# tin_of_fets.net
KiCad netlist of a schematic drawn in EAGLE
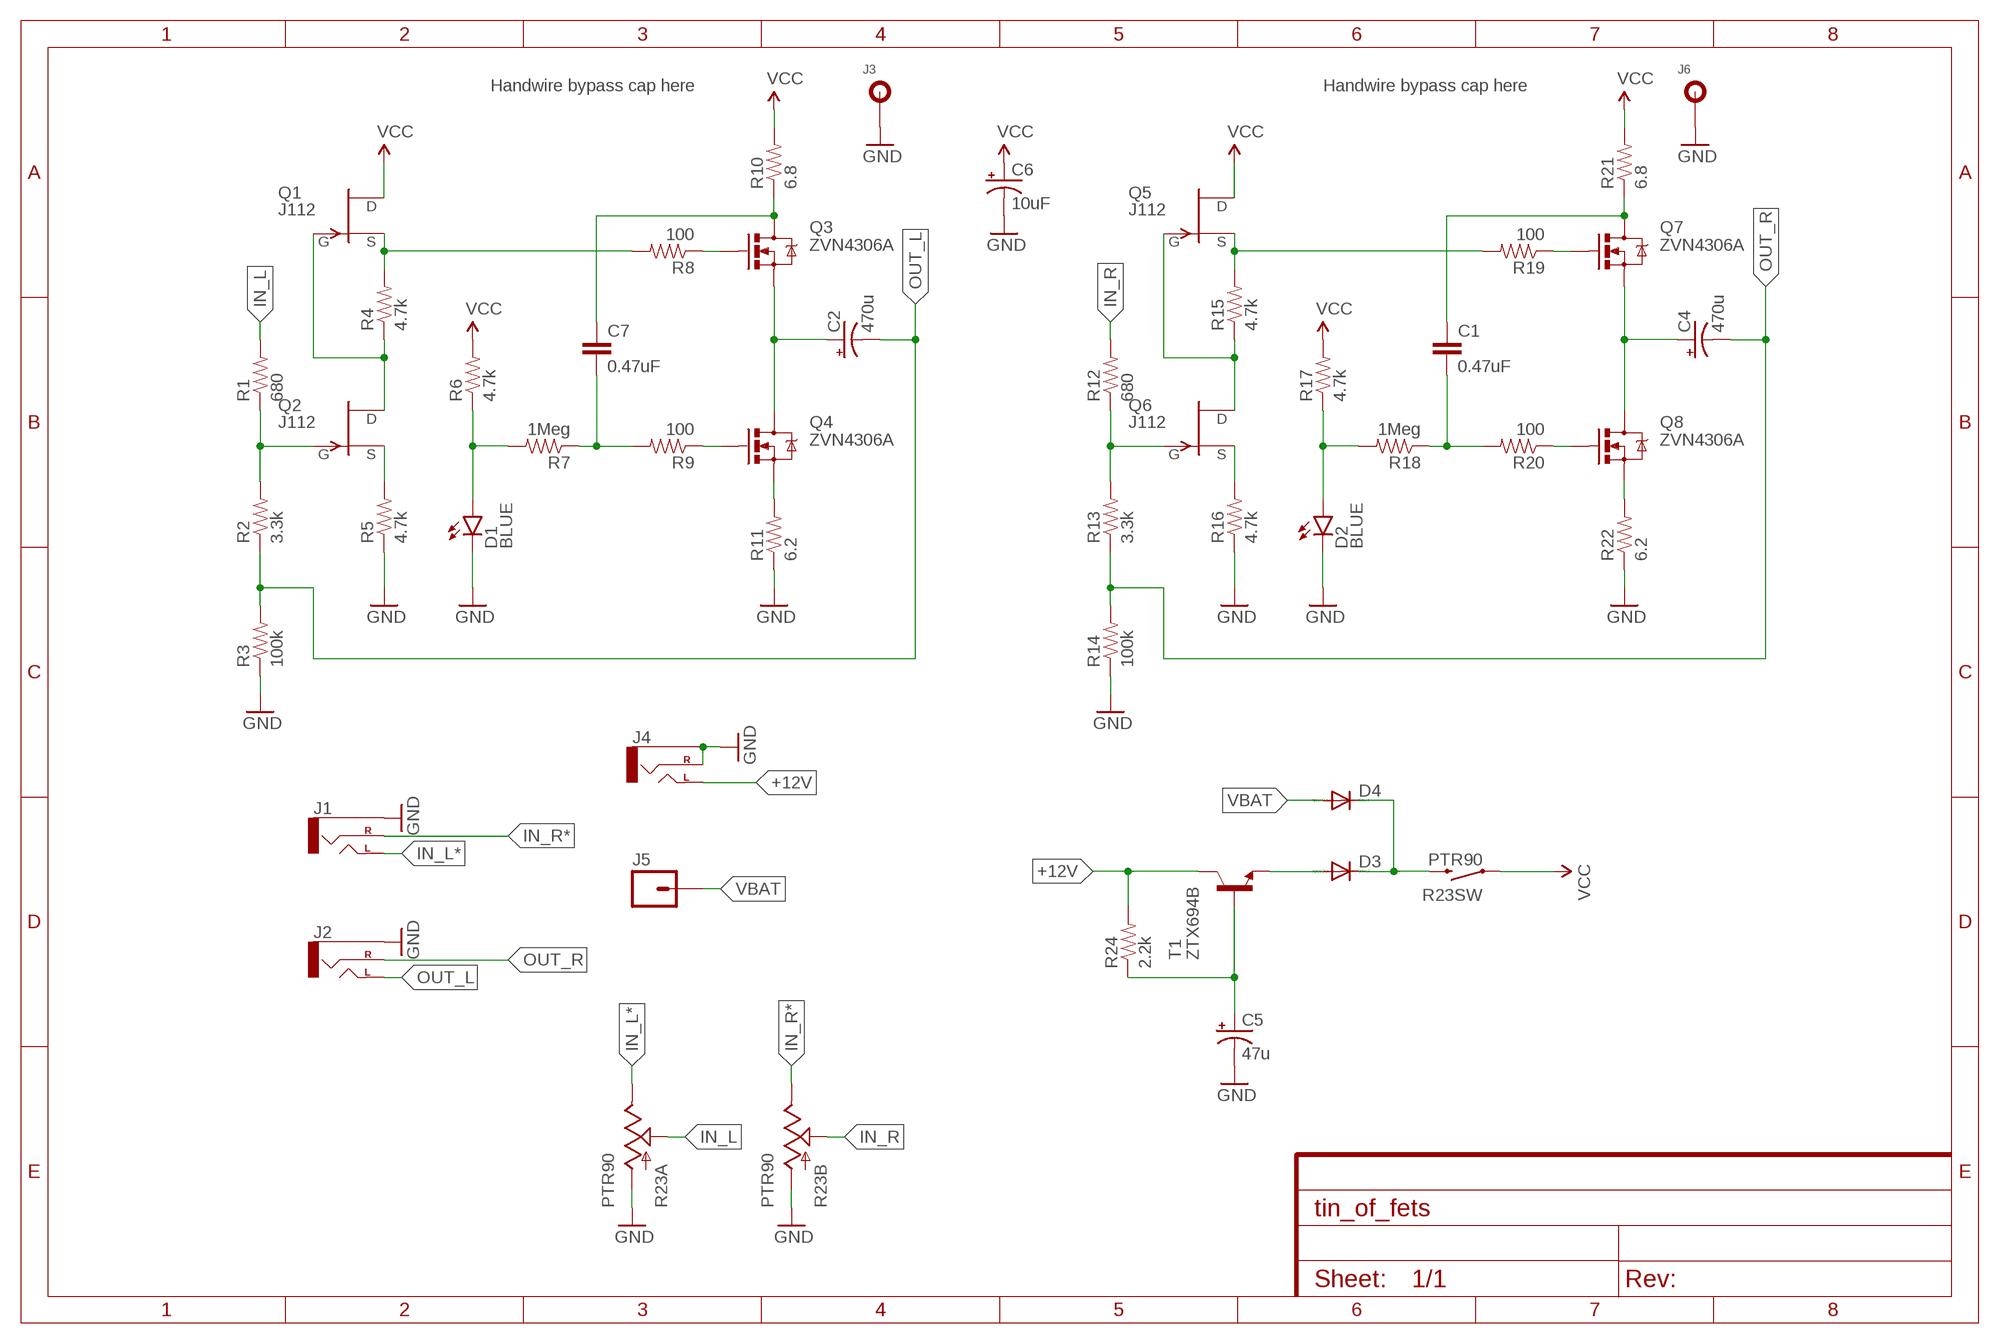
[diagram p0: schematic, sheet 1]

(export (version "E")
  (design (tool "Eeschema 10.0.6"))
  (components
    (comp (ref "A1")
      (value "9V-BATTERY-DOCU")
      (footprint "eagle-import:9V-BATTERY-DIM")
      (libsource (lib "eagle-import") (part "9V-BATTERY-DOCU"))
    )
    (comp (ref "A2")
      (value "9V-BATTERY-DOCU")
      (footprint "eagle-import:9V-BATTERY-DIM")
      (libsource (lib "eagle-import") (part "9V-BATTERY-DOCU"))
    )
    (comp (ref "A3")
      (value "ALTOIDS-DOCU")
      (footprint "eagle-import:ALTOIDS-INNER-DIM")
      (libsource (lib "eagle-import") (part "ALTOIDS-DOCU"))
    )
    (comp (ref "C1")
      (value "0.47uF")
      (footprint "eagle-import:C5B3.5")
      (libsource (lib "eagle-import") (part "C5/3.5"))
    )
    (comp (ref "C2")
      (value "470u")
      (footprint "eagle-import:CPOL-RADIAL-1000UF-25V")
      (libsource (lib "eagle-import") (part "CAP_POLPTH4"))
    )
    (comp (ref "C4")
      (value "470u")
      (footprint "eagle-import:CPOL-RADIAL-1000UF-25V")
      (libsource (lib "eagle-import") (part "CAP_POLPTH4"))
    )
    (comp (ref "C5")
      (value "47u")
      (footprint "eagle-import:CPOL-RADIAL-10UF-25V")
      (libsource (lib "eagle-import") (part "CAP_POLPTH2"))
    )
    (comp (ref "C6")
      (value "10uF")
      (footprint "eagle-import:CPOL-RADIAL-10UF-25V")
      (libsource (lib "eagle-import") (part "CAP_POLPTH2"))
    )
    (comp (ref "C7")
      (value "0.47uF")
      (footprint "eagle-import:C5B3.5")
      (libsource (lib "eagle-import") (part "C5/3.5"))
    )
    (comp (ref "D1")
      (value "BLUE")
      (footprint "eagle-import:LED3MM")
      (libsource (lib "eagle-import") (part "LED3MM"))
    )
    (comp (ref "D2")
      (value "BLUE")
      (footprint "eagle-import:LED3MM")
      (libsource (lib "eagle-import") (part "LED3MM"))
    )
    (comp (ref "D3")
      (value "DIODE-C1702-05")
      (footprint "eagle-import:C1702-05")
      (libsource (lib "eagle-import") (part "DIODE-C1702-05"))
    )
    (comp (ref "D4")
      (value "DIODE-C1702-05")
      (footprint "eagle-import:C1702-05")
      (libsource (lib "eagle-import") (part "DIODE-C1702-05"))
    )
    (comp (ref "J1")
      (value "AUDIO-JACK2.5MM")
      (footprint "eagle-import:STEREOJACK2.5MM_STEREOJACK2.5MM")
      (libsource (lib "eagle-import") (part "AUDIO-JACK2.5MM"))
    )
    (comp (ref "J2")
      (value "AUDIO-JACK2.5MM")
      (footprint "eagle-import:STEREOJACK2.5MM_STEREOJACK2.5MM")
      (libsource (lib "eagle-import") (part "AUDIO-JACK2.5MM"))
    )
    (comp (ref "J3")
      (value "PAD-NO-THERMAL")
      (footprint "eagle-import:PAD-NO-THERMAL")
      (libsource (lib "eagle-import") (part "PAD-NO-THERMAL"))
    )
    (comp (ref "J4")
      (value "AUDIO-JACK2.5MM")
      (footprint "eagle-import:STEREOJACK2.5MM_STEREOJACK2.5MM")
      (libsource (lib "eagle-import") (part "AUDIO-JACK2.5MM"))
    )
    (comp (ref "J5")
      (value "M01PTH")
      (footprint "eagle-import:1X01")
      (libsource (lib "eagle-import") (part "M01PTH"))
    )
    (comp (ref "J6")
      (value "PAD-NO-THERMAL")
      (footprint "eagle-import:PAD-NO-THERMAL")
      (libsource (lib "eagle-import") (part "PAD-NO-THERMAL"))
    )
    (comp (ref "Q1")
      (value "J112")
      (footprint "eagle-import:TO92")
      (libsource (lib "eagle-import") (part "?20J1"))
    )
    (comp (ref "Q2")
      (value "J112")
      (footprint "eagle-import:TO92")
      (libsource (lib "eagle-import") (part "?20J1"))
    )
    (comp (ref "Q3")
      (value "ZVN4306A")
      (footprint "eagle-import:TO-92")
      (libsource (lib "eagle-import") (part "MOSFET-NCHANNEL2N7000"))
    )
    (comp (ref "Q4")
      (value "ZVN4306A")
      (footprint "eagle-import:TO-92")
      (libsource (lib "eagle-import") (part "MOSFET-NCHANNEL2N7000"))
    )
    (comp (ref "Q5")
      (value "J112")
      (footprint "eagle-import:TO92")
      (libsource (lib "eagle-import") (part "?20J1"))
    )
    (comp (ref "Q6")
      (value "J112")
      (footprint "eagle-import:TO92")
      (libsource (lib "eagle-import") (part "?20J1"))
    )
    (comp (ref "Q7")
      (value "ZVN4306A")
      (footprint "eagle-import:TO-92")
      (libsource (lib "eagle-import") (part "MOSFET-NCHANNEL2N7000"))
    )
    (comp (ref "Q8")
      (value "ZVN4306A")
      (footprint "eagle-import:TO-92")
      (libsource (lib "eagle-import") (part "MOSFET-NCHANNEL2N7000"))
    )
    (comp (ref "R1")
      (value "680")
      (footprint "eagle-import:AXIAL-0.1-SM")
      (libsource (lib "eagle-import") (part "RESISTORPTH-1/4W-VERT-SM"))
    )
    (comp (ref "R2")
      (value "3.3k")
      (footprint "eagle-import:AXIAL-0.1-SM")
      (libsource (lib "eagle-import") (part "RESISTORPTH-1/4W-VERT-SM"))
    )
    (comp (ref "R3")
      (value "100k")
      (footprint "eagle-import:AXIAL-0.1-SM")
      (libsource (lib "eagle-import") (part "RESISTORPTH-1/4W-VERT-SM"))
    )
    (comp (ref "R4")
      (value "4.7k")
      (footprint "eagle-import:AXIAL-0.1-SM")
      (libsource (lib "eagle-import") (part "RESISTORPTH-1/4W-VERT-SM"))
    )
    (comp (ref "R5")
      (value "4.7k")
      (footprint "eagle-import:AXIAL-0.1-SM")
      (libsource (lib "eagle-import") (part "RESISTORPTH-1/4W-VERT-SM"))
    )
    (comp (ref "R6")
      (value "4.7k")
      (footprint "eagle-import:AXIAL-0.1-SM")
      (libsource (lib "eagle-import") (part "RESISTORPTH-1/4W-VERT-SM"))
    )
    (comp (ref "R7")
      (value "1Meg")
      (footprint "eagle-import:AXIAL-0.1-SM")
      (libsource (lib "eagle-import") (part "RESISTORPTH-1/4W-VERT-SM"))
    )
    (comp (ref "R8")
      (value "100")
      (footprint "eagle-import:AXIAL-0.1-SM")
      (libsource (lib "eagle-import") (part "RESISTORPTH-1/4W-VERT-SM"))
    )
    (comp (ref "R9")
      (value "100")
      (footprint "eagle-import:AXIAL-0.1-SM")
      (libsource (lib "eagle-import") (part "RESISTORPTH-1/4W-VERT-SM"))
    )
    (comp (ref "R10")
      (value "6.8")
      (footprint "eagle-import:AXIAL-0.1-SM")
      (libsource (lib "eagle-import") (part "RESISTORPTH-1/4W-VERT-SM"))
    )
    (comp (ref "R11")
      (value "6.2")
      (footprint "eagle-import:AXIAL-0.1-SM")
      (libsource (lib "eagle-import") (part "RESISTORPTH-1/4W-VERT-SM"))
    )
    (comp (ref "R12")
      (value "680")
      (footprint "eagle-import:AXIAL-0.1-SM")
      (libsource (lib "eagle-import") (part "RESISTORPTH-1/4W-VERT-SM"))
    )
    (comp (ref "R13")
      (value "3.3k")
      (footprint "eagle-import:AXIAL-0.1-SM")
      (libsource (lib "eagle-import") (part "RESISTORPTH-1/4W-VERT-SM"))
    )
    (comp (ref "R14")
      (value "100k")
      (footprint "eagle-import:AXIAL-0.1-SM")
      (libsource (lib "eagle-import") (part "RESISTORPTH-1/4W-VERT-SM"))
    )
    (comp (ref "R15")
      (value "4.7k")
      (footprint "eagle-import:AXIAL-0.1-SM")
      (libsource (lib "eagle-import") (part "RESISTORPTH-1/4W-VERT-SM"))
    )
    (comp (ref "R16")
      (value "4.7k")
      (footprint "eagle-import:AXIAL-0.1-SM")
      (libsource (lib "eagle-import") (part "RESISTORPTH-1/4W-VERT-SM"))
    )
    (comp (ref "R17")
      (value "4.7k")
      (footprint "eagle-import:AXIAL-0.1-SM")
      (libsource (lib "eagle-import") (part "RESISTORPTH-1/4W-VERT-SM"))
    )
    (comp (ref "R18")
      (value "1Meg")
      (footprint "eagle-import:AXIAL-0.1-SM")
      (libsource (lib "eagle-import") (part "RESISTORPTH-1/4W-VERT-SM"))
    )
    (comp (ref "R19")
      (value "100")
      (footprint "eagle-import:AXIAL-0.1-SM")
      (libsource (lib "eagle-import") (part "RESISTORPTH-1/4W-VERT-SM"))
    )
    (comp (ref "R20")
      (value "100")
      (footprint "eagle-import:AXIAL-0.1-SM")
      (libsource (lib "eagle-import") (part "RESISTORPTH-1/4W-VERT-SM"))
    )
    (comp (ref "R21")
      (value "6.8")
      (footprint "eagle-import:AXIAL-0.1-SM")
      (libsource (lib "eagle-import") (part "RESISTORPTH-1/4W-VERT-SM"))
    )
    (comp (ref "R22")
      (value "6.2")
      (footprint "eagle-import:AXIAL-0.1-SM")
      (libsource (lib "eagle-import") (part "RESISTORPTH-1/4W-VERT-SM"))
    )
    (comp (ref "R23")
      (value "PTR90")
      (footprint "eagle-import:PTR902")
      (libsource (lib "eagle-import") (part "PTR90"))
    )
    (comp (ref "R24")
      (value "2.2k")
      (footprint "eagle-import:AXIAL-0.1-SM")
      (libsource (lib "eagle-import") (part "RESISTORPTH-1/4W-VERT-SM"))
    )
    (comp (ref "T1")
      (value "ZTX694B")
      (footprint "eagle-import:TO92")
      (libsource (lib "eagle-import") (part "2N3565"))
    )
  )
  (nets
    (net (code "1") (name "+12V") (class "Default")
      (node (ref "J4") (pin "TIP") (pinfunction "LEFT_TIP") (pintype "bidirectional"))
      (node (ref "R24") (pin "P$2") (pinfunction "2_P$2") (pintype "passive"))
      (node (ref "T1") (pin "1") (pinfunction "C_1") (pintype "passive"))
    )
    (net (code "2") (name "GND") (class "Default")
      (node (ref "C5") (pin "2") (pinfunction "-_2") (pintype "passive"))
      (node (ref "C6") (pin "2") (pinfunction "-_2") (pintype "passive"))
      (node (ref "D1") (pin "K") (pinfunction "C_K") (pintype "passive"))
      (node (ref "D2") (pin "K") (pinfunction "C_K") (pintype "passive"))
      (node (ref "J1") (pin "SHIELD") (pinfunction "SLEEVE_SHIELD") (pintype "bidirectional"))
      (node (ref "J2") (pin "SHIELD") (pinfunction "SLEEVE_SHIELD") (pintype "bidirectional"))
      (node (ref "J3") (pin "P$1") (pinfunction "P$1_P$1") (pintype "bidirectional"))
      (node (ref "J4") (pin "RING1") (pinfunction "RIGHT_RING1") (pintype "bidirectional"))
      (node (ref "J4") (pin "RING2") (pinfunction "RIGHT_RING2") (pintype "bidirectional"))
      (node (ref "J4") (pin "SHIELD") (pinfunction "SLEEVE_SHIELD") (pintype "bidirectional"))
      (node (ref "J6") (pin "P$1") (pinfunction "P$1_P$1") (pintype "bidirectional"))
      (node (ref "R11") (pin "P$1") (pinfunction "1_P$1") (pintype "passive"))
      (node (ref "R14") (pin "P$1") (pinfunction "1_P$1") (pintype "passive"))
      (node (ref "R16") (pin "P$1") (pinfunction "1_P$1") (pintype "passive"))
      (node (ref "R22") (pin "P$1") (pinfunction "1_P$1") (pintype "passive"))
      (node (ref "R23") (pin "R1.1") (pinfunction "A_R1.1") (pintype "passive"))
      (node (ref "R23") (pin "R2.1") (pinfunction "A_R2.1") (pintype "passive"))
      (node (ref "R3") (pin "P$1") (pinfunction "1_P$1") (pintype "passive"))
      (node (ref "R5") (pin "P$1") (pinfunction "1_P$1") (pintype "passive"))
    )
    (net (code "3") (name "IN_L") (class "Default")
      (node (ref "R1") (pin "P$2") (pinfunction "2_P$2") (pintype "passive"))
      (node (ref "R23") (pin "R1.2") (pinfunction "S_R1.2") (pintype "passive"))
    )
    (net (code "4") (name "IN_L*") (class "Default")
      (node (ref "J1") (pin "TIP") (pinfunction "LEFT_TIP") (pintype "bidirectional"))
      (node (ref "R23") (pin "R1.3") (pinfunction "E_R1.3") (pintype "passive"))
    )
    (net (code "5") (name "IN_R") (class "Default")
      (node (ref "R12") (pin "P$2") (pinfunction "2_P$2") (pintype "passive"))
      (node (ref "R23") (pin "R2.2") (pinfunction "S_R2.2") (pintype "passive"))
    )
    (net (code "6") (name "IN_R*") (class "Default")
      (node (ref "J1") (pin "RING1") (pinfunction "RIGHT_RING1") (pintype "bidirectional"))
      (node (ref "J1") (pin "RING2") (pinfunction "RIGHT_RING2") (pintype "bidirectional"))
      (node (ref "R23") (pin "R2.3") (pinfunction "E_R2.3") (pintype "passive"))
    )
    (net (code "7") (name "Net-(C5-+)") (class "Default")
      (node (ref "C5") (pin "1") (pinfunction "+_1") (pintype "passive"))
      (node (ref "R24") (pin "P$1") (pinfunction "1_P$1") (pintype "passive"))
      (node (ref "T1") (pin "2") (pinfunction "B_2") (pintype "passive"))
    )
    (net (code "8") (name "Net-(Q1-G)") (class "Default")
      (node (ref "Q1") (pin "1") (pinfunction "G_1") (pintype "passive"))
      (node (ref "Q2") (pin "3") (pinfunction "D_3") (pintype "passive"))
      (node (ref "R4") (pin "P$1") (pinfunction "1_P$1") (pintype "passive"))
    )
    (net (code "9") (name "Net-(Q1-S)") (class "Default")
      (node (ref "Q1") (pin "2") (pinfunction "S_2") (pintype "passive"))
      (node (ref "R4") (pin "P$2") (pinfunction "2_P$2") (pintype "passive"))
      (node (ref "R8") (pin "P$2") (pinfunction "2_P$2") (pintype "passive"))
    )
    (net (code "10") (name "Net-(Q2-G)") (class "Default")
      (node (ref "Q2") (pin "1") (pinfunction "G_1") (pintype "passive"))
      (node (ref "R1") (pin "P$1") (pinfunction "1_P$1") (pintype "passive"))
      (node (ref "R2") (pin "P$2") (pinfunction "2_P$2") (pintype "passive"))
    )
    (net (code "11") (name "Net-(Q2-S)") (class "Default")
      (node (ref "Q2") (pin "2") (pinfunction "S_2") (pintype "passive"))
      (node (ref "R5") (pin "P$2") (pinfunction "2_P$2") (pintype "passive"))
    )
    (net (code "12") (name "Net-(Q3-D)") (class "Default")
      (node (ref "C7") (pin "1") (pinfunction "1_1") (pintype "passive"))
      (node (ref "Q3") (pin "3") (pinfunction "D_3") (pintype "passive"))
      (node (ref "R10") (pin "P$1") (pinfunction "1_P$1") (pintype "passive"))
    )
    (net (code "13") (name "Net-(Q3-G)") (class "Default")
      (node (ref "Q3") (pin "2") (pinfunction "G_2") (pintype "passive"))
      (node (ref "R8") (pin "P$1") (pinfunction "1_P$1") (pintype "passive"))
    )
    (net (code "14") (name "Net-(Q3-S)") (class "Default")
      (node (ref "C2") (pin "+") (pinfunction "+_+") (pintype "passive"))
      (node (ref "Q3") (pin "1") (pinfunction "S_1") (pintype "passive"))
      (node (ref "Q4") (pin "3") (pinfunction "D_3") (pintype "passive"))
    )
    (net (code "15") (name "Net-(Q4-G)") (class "Default")
      (node (ref "Q4") (pin "2") (pinfunction "G_2") (pintype "passive"))
      (node (ref "R9") (pin "P$1") (pinfunction "1_P$1") (pintype "passive"))
    )
    (net (code "16") (name "Net-(Q4-S)") (class "Default")
      (node (ref "Q4") (pin "1") (pinfunction "S_1") (pintype "passive"))
      (node (ref "R11") (pin "P$2") (pinfunction "2_P$2") (pintype "passive"))
    )
    (net (code "17") (name "Net-(Q5-G)") (class "Default")
      (node (ref "Q5") (pin "1") (pinfunction "G_1") (pintype "passive"))
      (node (ref "Q6") (pin "3") (pinfunction "D_3") (pintype "passive"))
      (node (ref "R15") (pin "P$1") (pinfunction "1_P$1") (pintype "passive"))
    )
    (net (code "18") (name "Net-(Q5-S)") (class "Default")
      (node (ref "Q5") (pin "2") (pinfunction "S_2") (pintype "passive"))
      (node (ref "R15") (pin "P$2") (pinfunction "2_P$2") (pintype "passive"))
      (node (ref "R19") (pin "P$2") (pinfunction "2_P$2") (pintype "passive"))
    )
    (net (code "19") (name "Net-(Q6-G)") (class "Default")
      (node (ref "Q6") (pin "1") (pinfunction "G_1") (pintype "passive"))
      (node (ref "R12") (pin "P$1") (pinfunction "1_P$1") (pintype "passive"))
      (node (ref "R13") (pin "P$2") (pinfunction "2_P$2") (pintype "passive"))
    )
    (net (code "20") (name "Net-(Q6-S)") (class "Default")
      (node (ref "Q6") (pin "2") (pinfunction "S_2") (pintype "passive"))
      (node (ref "R16") (pin "P$2") (pinfunction "2_P$2") (pintype "passive"))
    )
    (net (code "21") (name "Net-(Q7-D)") (class "Default")
      (node (ref "C1") (pin "1") (pinfunction "1_1") (pintype "passive"))
      (node (ref "Q7") (pin "3") (pinfunction "D_3") (pintype "passive"))
      (node (ref "R21") (pin "P$1") (pinfunction "1_P$1") (pintype "passive"))
    )
    (net (code "22") (name "Net-(Q7-G)") (class "Default")
      (node (ref "Q7") (pin "2") (pinfunction "G_2") (pintype "passive"))
      (node (ref "R19") (pin "P$1") (pinfunction "1_P$1") (pintype "passive"))
    )
    (net (code "23") (name "Net-(Q7-S)") (class "Default")
      (node (ref "C4") (pin "+") (pinfunction "+_+") (pintype "passive"))
      (node (ref "Q7") (pin "1") (pinfunction "S_1") (pintype "passive"))
      (node (ref "Q8") (pin "3") (pinfunction "D_3") (pintype "passive"))
    )
    (net (code "24") (name "Net-(Q8-G)") (class "Default")
      (node (ref "Q8") (pin "2") (pinfunction "G_2") (pintype "passive"))
      (node (ref "R20") (pin "P$1") (pinfunction "1_P$1") (pintype "passive"))
    )
    (net (code "25") (name "Net-(Q8-S)") (class "Default")
      (node (ref "Q8") (pin "1") (pinfunction "S_1") (pintype "passive"))
      (node (ref "R22") (pin "P$2") (pinfunction "2_P$2") (pintype "passive"))
    )
    (net (code "26") (name "Net-(R6-1)") (class "Default")
      (node (ref "D1") (pin "A") (pinfunction "A_A") (pintype "passive"))
      (node (ref "R6") (pin "P$1") (pinfunction "1_P$1") (pintype "passive"))
      (node (ref "R7") (pin "P$2") (pinfunction "2_P$2") (pintype "passive"))
    )
    (net (code "27") (name "Net-(R7-1)") (class "Default")
      (node (ref "C7") (pin "2") (pinfunction "2_2") (pintype "passive"))
      (node (ref "R7") (pin "P$1") (pinfunction "1_P$1") (pintype "passive"))
      (node (ref "R9") (pin "P$2") (pinfunction "2_P$2") (pintype "passive"))
    )
    (net (code "28") (name "Net-(R17-1)") (class "Default")
      (node (ref "D2") (pin "A") (pinfunction "A_A") (pintype "passive"))
      (node (ref "R17") (pin "P$1") (pinfunction "1_P$1") (pintype "passive"))
      (node (ref "R18") (pin "P$2") (pinfunction "2_P$2") (pintype "passive"))
    )
    (net (code "29") (name "Net-(R18-1)") (class "Default")
      (node (ref "C1") (pin "2") (pinfunction "2_2") (pintype "passive"))
      (node (ref "R18") (pin "P$1") (pinfunction "1_P$1") (pintype "passive"))
      (node (ref "R20") (pin "P$2") (pinfunction "2_P$2") (pintype "passive"))
    )
    (net (code "30") (name "Net-(R23C-2)") (class "Default")
      (node (ref "D3") (pin "C") (pinfunction "C_C") (pintype "passive"))
      (node (ref "D4") (pin "C") (pinfunction "C_C") (pintype "passive"))
      (node (ref "R23") (pin "SW2") (pinfunction "2_SW2") (pintype "passive"))
    )
    (net (code "31") (name "Net-(T1-E)") (class "Default")
      (node (ref "D3") (pin "A") (pinfunction "A_A") (pintype "passive"))
      (node (ref "T1") (pin "3") (pinfunction "E_3") (pintype "passive"))
    )
    (net (code "32") (name "OUT_L") (class "Default")
      (node (ref "C2") (pin "-") (pinfunction "-_-") (pintype "passive"))
      (node (ref "J2") (pin "TIP") (pinfunction "LEFT_TIP") (pintype "bidirectional"))
      (node (ref "R2") (pin "P$1") (pinfunction "1_P$1") (pintype "passive"))
      (node (ref "R3") (pin "P$2") (pinfunction "2_P$2") (pintype "passive"))
    )
    (net (code "33") (name "OUT_R") (class "Default")
      (node (ref "C4") (pin "-") (pinfunction "-_-") (pintype "passive"))
      (node (ref "J2") (pin "RING1") (pinfunction "RIGHT_RING1") (pintype "bidirectional"))
      (node (ref "J2") (pin "RING2") (pinfunction "RIGHT_RING2") (pintype "bidirectional"))
      (node (ref "R13") (pin "P$1") (pinfunction "1_P$1") (pintype "passive"))
      (node (ref "R14") (pin "P$2") (pinfunction "2_P$2") (pintype "passive"))
    )
    (net (code "34") (name "VBAT") (class "Default")
      (node (ref "D4") (pin "A") (pinfunction "A_A") (pintype "passive"))
      (node (ref "J5") (pin "1") (pinfunction "1_1") (pintype "passive"))
    )
    (net (code "35") (name "VCC") (class "Default")
      (node (ref "C6") (pin "1") (pinfunction "+_1") (pintype "passive"))
      (node (ref "Q1") (pin "3") (pinfunction "D_3") (pintype "passive"))
      (node (ref "Q5") (pin "3") (pinfunction "D_3") (pintype "passive"))
      (node (ref "R10") (pin "P$2") (pinfunction "2_P$2") (pintype "passive"))
      (node (ref "R17") (pin "P$2") (pinfunction "2_P$2") (pintype "passive"))
      (node (ref "R21") (pin "P$2") (pinfunction "2_P$2") (pintype "passive"))
      (node (ref "R23") (pin "SW1") (pinfunction "1_SW1") (pintype "passive"))
      (node (ref "R6") (pin "P$2") (pinfunction "2_P$2") (pintype "passive"))
    )
  )
)
